# IsolatedDAC.net
KiCad netlist of a schematic drawn in Altium Designer
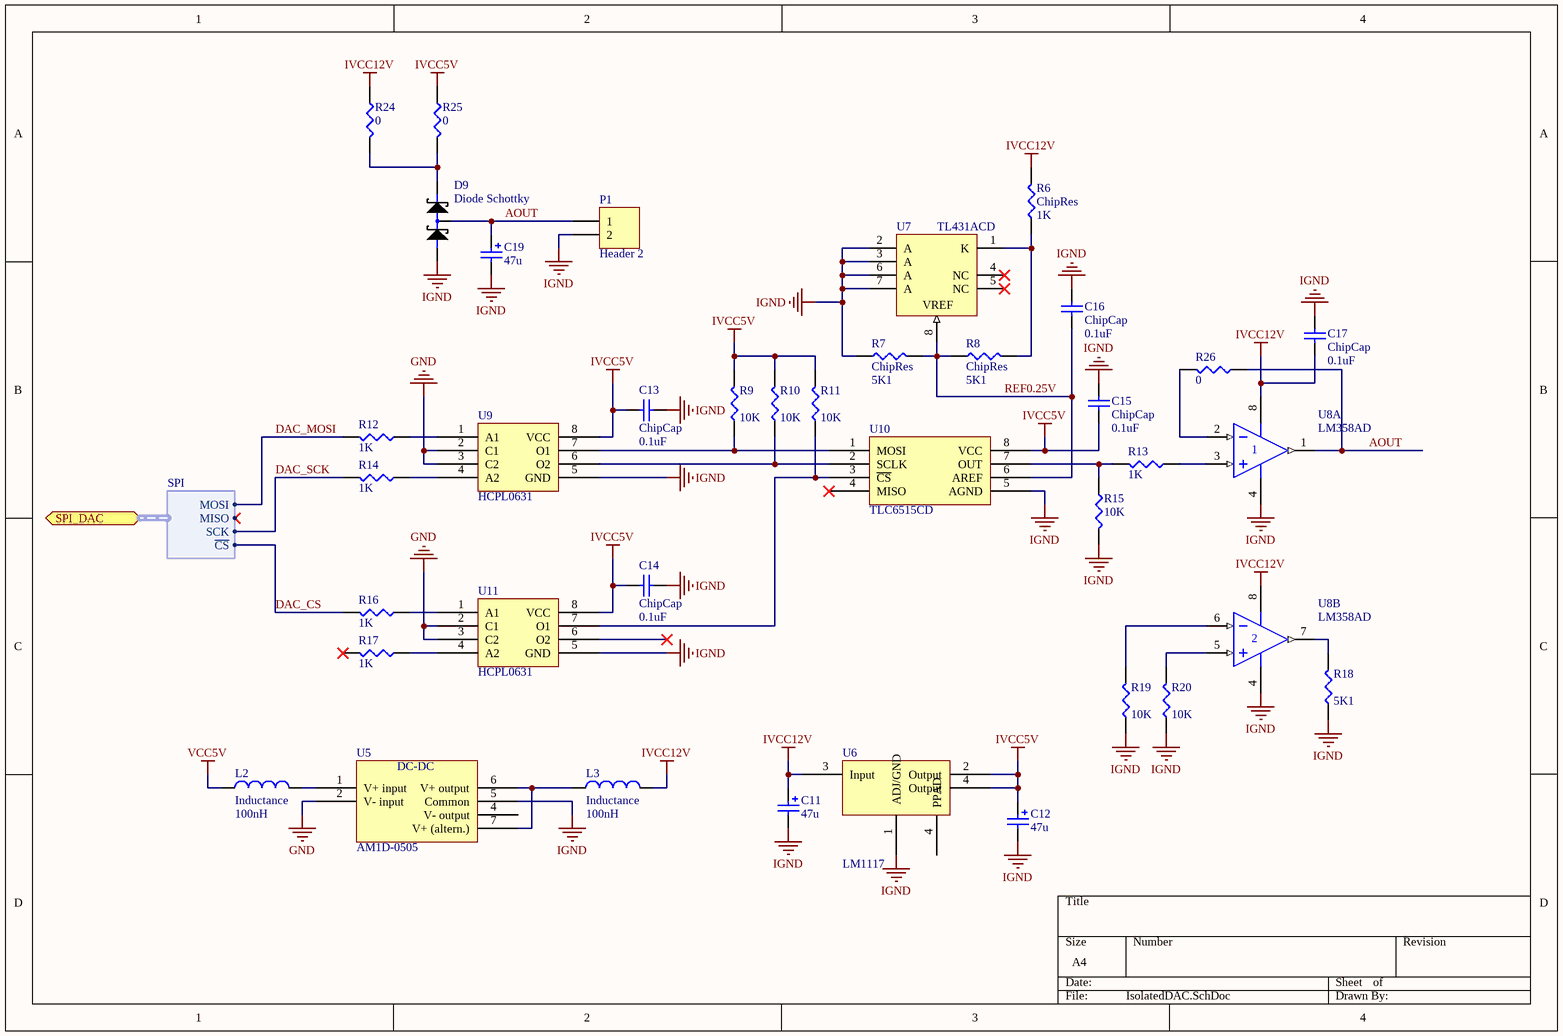
[diagram p0: IsolatedDAC.SchDoc]

(export (version "E")
  (design (tool "Eeschema 10.0.6"))
  (components
    (comp (ref "C11")
      (value "47u")
      (footprint "CAPC7343")
      (description "Polarized Capacitor (Radial)")
      (fields (field (name "Comment") "Cap Pol SMD"))
      (libsource (lib "Common Devices") (part "Cap Pol Chip"))
    )
    (comp (ref "C12")
      (value "47u")
      (footprint "CAPC7343")
      (description "Polarized Capacitor (Radial)")
      (fields (field (name "Comment") "Cap Pol SMD"))
      (libsource (lib "Common Devices") (part "Cap Pol Chip"))
    )
    (comp (ref "C13")
      (value "ChipCap")
      (footprint "CAP0805")
      (description "Capacitor")
      (fields (field (name "ALTIUM_VALUE") "0.1uF") (field (name "PUBLISHER") "Altium Limited"))
      (libsource (lib "Common Devices") (part "ChipCap"))
    )
    (comp (ref "C14")
      (value "ChipCap")
      (footprint "CAP0805")
      (description "Capacitor")
      (fields (field (name "ALTIUM_VALUE") "0.1uF") (field (name "PUBLISHER") "Altium Limited"))
      (libsource (lib "Common Devices") (part "ChipCap"))
    )
    (comp (ref "C15")
      (value "ChipCap")
      (footprint "CAP0805")
      (description "Capacitor")
      (fields (field (name "ALTIUM_VALUE") "0.1uF") (field (name "PUBLISHER") "Altium Limited"))
      (libsource (lib "Common Devices") (part "ChipCap"))
    )
    (comp (ref "C16")
      (value "ChipCap")
      (footprint "CAP0805")
      (description "Capacitor")
      (fields (field (name "ALTIUM_VALUE") "0.1uF") (field (name "PUBLISHER") "Altium Limited"))
      (libsource (lib "Common Devices") (part "ChipCap"))
    )
    (comp (ref "C17")
      (value "ChipCap")
      (footprint "CAP0805")
      (description "Capacitor")
      (fields (field (name "ALTIUM_VALUE") "0.1uF") (field (name "PUBLISHER") "Altium Limited"))
      (libsource (lib "Common Devices") (part "ChipCap"))
    )
    (comp (ref "C19")
      (value "47u")
      (footprint "CAPC7343")
      (description "Polarized Capacitor (Radial)")
      (fields (field (name "Comment") "Cap Pol SMD"))
      (libsource (lib "Common Devices") (part "Cap Pol Chip"))
    )
    (comp (ref "D9")
      (value "Diode Schottky")
      (footprint "SOT23")
      (description "2-Diode Schottky")
      (libsource (lib "Protection") (part "Schottky Diode"))
    )
    (comp (ref "L2")
      (value "Inductance")
      (footprint "CM32")
      (fields (field (name "ALTIUM_VALUE") "100nH"))
      (libsource (lib "Common Devices") (part "ChipInductance"))
    )
    (comp (ref "L3")
      (value "Inductance")
      (footprint "CM32")
      (fields (field (name "ALTIUM_VALUE") "100nH"))
      (libsource (lib "Common Devices") (part "ChipInductance"))
    )
    (comp (ref "P1")
      (value "Header 2")
      (footprint "HDR1X2")
      (description "Header, 2-Pin")
      (fields (field (name "PUBLISHER") "Altium Limited"))
      (libsource (lib "Miscellaneous Connectors") (part "Header 2"))
    )
    (comp (ref "R6")
      (value "ChipRes")
      (footprint "RES0805")
      (description "Chip resistor")
      (fields (field (name "ALTIUM_VALUE") "1K"))
      (libsource (lib "Common Devices") (part "ChipRes"))
    )
    (comp (ref "R7")
      (value "ChipRes")
      (footprint "RES0805")
      (description "Chip resistor")
      (fields (field (name "ALTIUM_VALUE") "5K1"))
      (libsource (lib "Common Devices") (part "ChipRes"))
    )
    (comp (ref "R8")
      (value "ChipRes")
      (footprint "RES0805")
      (description "Chip resistor")
      (fields (field (name "ALTIUM_VALUE") "5K1"))
      (libsource (lib "Common Devices") (part "ChipRes"))
    )
    (comp (ref "R9")
      (value "10K")
      (footprint "RES0805")
      (description "Chip resistor")
      (fields (field (name "Comment") "ChipRes"))
      (libsource (lib "Common Devices") (part "ChipRes"))
    )
    (comp (ref "R10")
      (value "10K")
      (footprint "RES0805")
      (description "Chip resistor")
      (fields (field (name "Comment") "ChipRes"))
      (libsource (lib "Common Devices") (part "ChipRes"))
    )
    (comp (ref "R11")
      (value "10K")
      (footprint "RES0805")
      (description "Chip resistor")
      (fields (field (name "Comment") "ChipRes"))
      (libsource (lib "Common Devices") (part "ChipRes"))
    )
    (comp (ref "R12")
      (value "1K")
      (footprint "RES0805")
      (description "Chip resistor")
      (fields (field (name "Comment") "ChipRes"))
      (libsource (lib "Common Devices") (part "ChipRes"))
    )
    (comp (ref "R13")
      (value "1K")
      (footprint "RES0805")
      (description "Chip resistor")
      (fields (field (name "Comment") "ChipRes"))
      (libsource (lib "Common Devices") (part "ChipRes"))
    )
    (comp (ref "R14")
      (value "1K")
      (footprint "RES0805")
      (description "Chip resistor")
      (fields (field (name "Comment") "ChipRes"))
      (libsource (lib "Common Devices") (part "ChipRes"))
    )
    (comp (ref "R15")
      (value "10K")
      (footprint "RES0805")
      (description "Chip resistor")
      (fields (field (name "Comment") "ChipRes"))
      (libsource (lib "Common Devices") (part "ChipRes"))
    )
    (comp (ref "R16")
      (value "1K")
      (footprint "RES0805")
      (description "Chip resistor")
      (fields (field (name "Comment") "ChipRes"))
      (libsource (lib "Common Devices") (part "ChipRes"))
    )
    (comp (ref "R17")
      (value "1K")
      (footprint "RES0805")
      (description "Chip resistor")
      (fields (field (name "Comment") "ChipRes"))
      (libsource (lib "Common Devices") (part "ChipRes"))
    )
    (comp (ref "R18")
      (value "5K1")
      (footprint "RES0805")
      (description "Chip resistor")
      (fields (field (name "Comment") "ChipRes"))
      (libsource (lib "Common Devices") (part "ChipRes"))
    )
    (comp (ref "R19")
      (value "10K")
      (footprint "RES0805")
      (description "Chip resistor")
      (fields (field (name "Comment") "ChipRes"))
      (libsource (lib "Common Devices") (part "ChipRes"))
    )
    (comp (ref "R20")
      (value "10K")
      (footprint "RES0805")
      (description "Chip resistor")
      (fields (field (name "Comment") "ChipRes"))
      (libsource (lib "Common Devices") (part "ChipRes"))
    )
    (comp (ref "R24")
      (value "0")
      (footprint "RES0805")
      (description "Chip resistor")
      (fields (field (name "Comment") "ChipRes"))
      (libsource (lib "Common Devices") (part "ChipRes"))
    )
    (comp (ref "R25")
      (value "0")
      (footprint "RES0805")
      (description "Chip resistor")
      (fields (field (name "Comment") "ChipRes"))
      (libsource (lib "Common Devices") (part "ChipRes"))
    )
    (comp (ref "R26")
      (value "0")
      (footprint "RES0805")
      (description "Chip resistor")
      (fields (field (name "Comment") "ChipRes"))
      (libsource (lib "Common Devices") (part "ChipRes"))
    )
    (comp (ref "U5")
      (value "AM1D-0505")
      (footprint "SIP14")
      (description "DC-DC 5-12V convertor")
      (libsource (lib "Aimtec DC-DC converter") (part "AM1D-0512"))
    )
    (comp (ref "U6")
      (value "LM1117")
      (footprint "SOT223-4M")
      (description "Power Mgt Voltage Regulator")
      (libsource (lib "TI Step Motor Driver") (part "LM1117"))
    )
    (comp (ref "U7")
      (value "TL431ACD")
      (footprint "D008_N")
      (description "Adjustable Precision Shunt Regulator")
      (fields (field (name "PUBLISHER") "Altium Limited"))
      (libsource (lib "TI Power Mgt Voltage Regulator") (part "TL431ACD"))
    )
    (comp (ref "U8")
      (value "LM358AD")
      (footprint "D008_L")
      (description "Dual Operational Amplifier")
      (fields (field (name "PUBLISHER") "Altium Limited"))
      (libsource (lib "TI Operational Amplifier") (part "LM358AD"))
    )
    (comp (ref "U9")
      (value "HCPL0631")
      (footprint "SOIC8")
      (description "2-channel opto-coupler")
      (libsource (lib "Avago Optocouplers") (part "HCPL0631"))
    )
    (comp (ref "U10")
      (value "TLC6515CD")
      (footprint "SOIC8")
      (description "10-bit analog to digiyal converter")
      (fields (field (name "MANUFACTURER") "Texas Instruments"))
      (libsource (lib "TI_DigitalToAnalogConverters") (part "TLC6515"))
    )
    (comp (ref "U11")
      (value "HCPL0631")
      (footprint "SOIC8")
      (description "2-channel opto-coupler")
      (libsource (lib "Avago Optocouplers") (part "HCPL0631"))
    )
  )
  (nets
    (net (code "2") (name "/AOUT") (class "Default")
      (node (ref "C19") (pin "1") (pinfunction "1_1") (pintype "passive"))
      (node (ref "D9") (pin "3") (pinfunction "3_3") (pintype "passive"))
      (node (ref "P1") (pin "1") (pinfunction "1_1") (pintype "passive"))
      (node (ref "R26") (pin "1") (pintype "passive"))
      (node (ref "U8") (pin "1") (pinfunction "OUT_1") (pintype "output"))
    )
    (net (code "3") (name "/DAC_CS") (class "Default") (node (ref "R16") (pin "2") (pintype "passive")))
    (net (code "4") (name "/DAC_MOSI") (class "Default") (node (ref "R12") (pin "2") (pintype "passive")))
    (net (code "5") (name "/DAC_SCK") (class "Default") (node (ref "R14") (pin "2") (pintype "passive")))
    (net (code "6") (name "/REF0.25V") (class "Default")
      (node (ref "C16") (pin "2") (pinfunction "2_2") (pintype "passive"))
      (node (ref "R7") (pin "2") (pintype "passive"))
      (node (ref "R8") (pin "1") (pintype "passive"))
      (node (ref "U10") (pin "6") (pinfunction "AREF_6") (pintype "passive"))
      (node (ref "U7") (pin "8") (pinfunction "VREF_8") (pintype "input"))
    )
    (net (code "8") (name "GND") (class "Default")
      (node (ref "U11") (pin "2") (pinfunction "C1_2") (pintype "passive"))
      (node (ref "U11") (pin "3") (pinfunction "C2_3") (pintype "passive"))
      (node (ref "U5") (pin "2") (pinfunction "V-_input_2") (pintype "passive"))
      (node (ref "U9") (pin "2") (pinfunction "C1_2") (pintype "passive"))
      (node (ref "U9") (pin "3") (pinfunction "C2_3") (pintype "passive"))
    )
    (net (code "9") (name "IGND") (class "Default")
      (node (ref "C11") (pin "2") (pinfunction "2_2") (pintype "passive"))
      (node (ref "C12") (pin "2") (pinfunction "2_2") (pintype "passive"))
      (node (ref "C13") (pin "1") (pinfunction "1_1") (pintype "passive"))
      (node (ref "C14") (pin "1") (pinfunction "1_1") (pintype "passive"))
      (node (ref "C15") (pin "1") (pinfunction "1_1") (pintype "passive"))
      (node (ref "C16") (pin "1") (pinfunction "1_1") (pintype "passive"))
      (node (ref "C17") (pin "1") (pinfunction "1_1") (pintype "passive"))
      (node (ref "C19") (pin "2") (pinfunction "2_2") (pintype "passive"))
      (node (ref "D9") (pin "1") (pinfunction "1_1") (pintype "passive"))
      (node (ref "P1") (pin "2") (pinfunction "2_2") (pintype "passive"))
      (node (ref "R15") (pin "2") (pintype "passive"))
      (node (ref "R18") (pin "1") (pintype "passive"))
      (node (ref "R19") (pin "1") (pintype "passive"))
      (node (ref "R20") (pin "1") (pintype "passive"))
      (node (ref "R7") (pin "1") (pintype "passive"))
      (node (ref "U10") (pin "5") (pinfunction "AGND_5") (pintype "passive"))
      (node (ref "U11") (pin "5") (pinfunction "GND_5") (pintype "passive"))
      (node (ref "U5") (pin "5") (pinfunction "Common_5") (pintype "passive"))
      (node (ref "U6") (pin "1") (pinfunction "ADJ/GND_1") (pintype "power_in"))
      (node (ref "U7") (pin "2") (pinfunction "A_2") (pintype "power_in"))
      (node (ref "U7") (pin "3") (pinfunction "A_3") (pintype "power_in"))
      (node (ref "U7") (pin "6") (pinfunction "A_6") (pintype "power_in"))
      (node (ref "U7") (pin "7") (pinfunction "A_7") (pintype "power_in"))
      (node (ref "U8") (pin "4") (pinfunction "V-_4") (pintype "power_in"))
      (node (ref "U9") (pin "5") (pinfunction "GND_5") (pintype "passive"))
    )
    (net (code "10") (name "IVCC5V") (class "Default")
      (node (ref "C12") (pin "1") (pinfunction "1_1") (pintype "passive"))
      (node (ref "C13") (pin "2") (pinfunction "2_2") (pintype "passive"))
      (node (ref "C14") (pin "2") (pinfunction "2_2") (pintype "passive"))
      (node (ref "C15") (pin "2") (pinfunction "2_2") (pintype "passive"))
      (node (ref "R10") (pin "2") (pintype "passive"))
      (node (ref "R11") (pin "2") (pintype "passive"))
      (node (ref "R25") (pin "1") (pintype "passive"))
      (node (ref "R9") (pin "2") (pintype "passive"))
      (node (ref "U10") (pin "8") (pinfunction "VCC_8") (pintype "passive"))
      (node (ref "U11") (pin "8") (pinfunction "VCC_8") (pintype "passive"))
      (node (ref "U6") (pin "2") (pinfunction "Output_2") (pintype "power_in"))
      (node (ref "U6") (pin "4") (pinfunction "Output_4") (pintype "power_in"))
      (node (ref "U9") (pin "8") (pinfunction "VCC_8") (pintype "passive"))
    )
    (net (code "11") (name "IVCC12V") (class "Default")
      (node (ref "C11") (pin "1") (pinfunction "1_1") (pintype "passive"))
      (node (ref "C17") (pin "2") (pinfunction "2_2") (pintype "passive"))
      (node (ref "L3") (pin "1") (pintype "passive"))
      (node (ref "R24") (pin "1") (pintype "passive"))
      (node (ref "R6") (pin "2") (pintype "passive"))
      (node (ref "U6") (pin "3") (pinfunction "Input_3") (pintype "power_in"))
      (node (ref "U8") (pin "8") (pinfunction "V+_8") (pintype "power_in"))
    )
    (net (code "12") (name "Net-(D9-Pad2)") (class "Default")
      (node (ref "D9") (pin "2") (pinfunction "2_2") (pintype "passive"))
      (node (ref "R24") (pin "2") (pintype "passive"))
      (node (ref "R25") (pin "2") (pintype "passive"))
    )
    (net (code "13") (name "Net-(U5-V+_(altern.))") (class "Default")
      (node (ref "L3") (pin "2") (pintype "passive"))
      (node (ref "U5") (pin "6") (pinfunction "V+_output_6") (pintype "passive"))
      (node (ref "U5") (pin "7") (pinfunction "V+_(altern.)_7") (pintype "passive"))
    )
    (net (code "14") (name "Net-(U5-V+_input)") (class "Default")
      (node (ref "L2") (pin "1") (pintype "passive"))
      (node (ref "U5") (pin "1") (pinfunction "V+_input_1") (pintype "passive"))
    )
    (net (code "15") (name "Net-(U7-K)") (class "Default")
      (node (ref "R6") (pin "1") (pintype "passive"))
      (node (ref "R8") (pin "2") (pintype "passive"))
      (node (ref "U7") (pin "1") (pinfunction "K_1") (pintype "power_in"))
    )
    (net (code "16") (name "Net-(U8A-IN+)") (class "Default")
      (node (ref "R13") (pin "1") (pintype "passive"))
      (node (ref "U8") (pin "3") (pinfunction "IN+_3") (pintype "input"))
    )
    (net (code "17") (name "Net-(U8A-IN-)") (class "Default")
      (node (ref "R26") (pin "2") (pintype "passive"))
      (node (ref "U8") (pin "2") (pinfunction "IN-_2") (pintype "input"))
    )
    (net (code "18") (name "Net-(U8B-IN+)") (class "Default")
      (node (ref "R20") (pin "2") (pintype "passive"))
      (node (ref "U8") (pin "5") (pinfunction "IN+_5") (pintype "input"))
    )
    (net (code "19") (name "Net-(U8B-IN-)") (class "Default")
      (node (ref "R19") (pin "2") (pintype "passive"))
      (node (ref "U8") (pin "6") (pinfunction "IN-_6") (pintype "input"))
    )
    (net (code "20") (name "Net-(U8B-OUT)") (class "Default")
      (node (ref "R18") (pin "2") (pintype "passive"))
      (node (ref "U8") (pin "7") (pinfunction "OUT_7") (pintype "output"))
    )
    (net (code "21") (name "Net-(U9-A1)") (class "Default")
      (node (ref "R12") (pin "1") (pintype "passive"))
      (node (ref "U9") (pin "1") (pinfunction "A1_1") (pintype "passive"))
    )
    (net (code "22") (name "Net-(U9-A2)") (class "Default")
      (node (ref "R14") (pin "1") (pintype "passive"))
      (node (ref "U9") (pin "4") (pinfunction "A2_4") (pintype "passive"))
    )
    (net (code "23") (name "Net-(U10-MOSI)") (class "Default")
      (node (ref "R9") (pin "1") (pintype "passive"))
      (node (ref "U10") (pin "1") (pinfunction "MOSI_1") (pintype "passive"))
      (node (ref "U9") (pin "7") (pinfunction "O1_7") (pintype "passive"))
    )
    (net (code "24") (name "Net-(U10-OUT)") (class "Default")
      (node (ref "R13") (pin "2") (pintype "passive"))
      (node (ref "R15") (pin "1") (pintype "passive"))
      (node (ref "U10") (pin "7") (pinfunction "OUT_7") (pintype "passive"))
    )
    (net (code "25") (name "Net-(U10-SCLK)") (class "Default")
      (node (ref "R10") (pin "1") (pintype "passive"))
      (node (ref "U10") (pin "2") (pinfunction "SCLK_2") (pintype "passive"))
      (node (ref "U9") (pin "6") (pinfunction "O2_6") (pintype "passive"))
    )
    (net (code "26") (name "Net-(U10-~{CS})") (class "Default")
      (node (ref "R11") (pin "1") (pintype "passive"))
      (node (ref "U10") (pin "3") (pinfunction "~{CS}_3") (pintype "passive"))
      (node (ref "U11") (pin "7") (pinfunction "O1_7") (pintype "passive"))
    )
    (net (code "27") (name "Net-(U11-A1)") (class "Default")
      (node (ref "R16") (pin "1") (pintype "passive"))
      (node (ref "U11") (pin "1") (pinfunction "A1_1") (pintype "passive"))
    )
    (net (code "28") (name "Net-(U11-A2)") (class "Default")
      (node (ref "R17") (pin "1") (pintype "passive"))
      (node (ref "U11") (pin "4") (pinfunction "A2_4") (pintype "passive"))
    )
    (net (code "29") (name "VCC5V") (class "Default") (node (ref "L2") (pin "2") (pintype "passive")))
    (net (code "30") (name "unconnected-(R17-Pad2)") (class "Default")
      (node (ref "R17") (pin "2") (pintype "passive+no_connect"))
    )
    (net (code "31") (name "unconnected-(U5-V-_output-Pad4)") (class "Default")
      (node (ref "U5") (pin "4") (pinfunction "V-_output_4") (pintype "passive"))
    )
    (net (code "32") (name "unconnected-(U6-PPAD-Pad4)") (class "Default")
      (node (ref "U6") (pin "4") (pinfunction "PPAD_4") (pintype "passive"))
    )
    (net (code "33") (name "unconnected-(U7-NC-Pad4)") (class "Default")
      (node (ref "U7") (pin "4") (pinfunction "NC_4") (pintype "passive+no_connect"))
    )
    (net (code "34") (name "unconnected-(U7-NC-Pad5)") (class "Default")
      (node (ref "U7") (pin "5") (pinfunction "NC_5") (pintype "passive+no_connect"))
    )
    (net (code "35") (name "unconnected-(U10-MISO-Pad4)") (class "Default")
      (node (ref "U10") (pin "4") (pinfunction "MISO_4") (pintype "passive+no_connect"))
    )
    (net (code "36") (name "unconnected-(U11-O2-Pad6)") (class "Default")
      (node (ref "U11") (pin "6") (pinfunction "O2_6") (pintype "passive+no_connect"))
    )
  )
)
